# Sheet1.net
KiCad netlist of a schematic drawn in Altium Designer
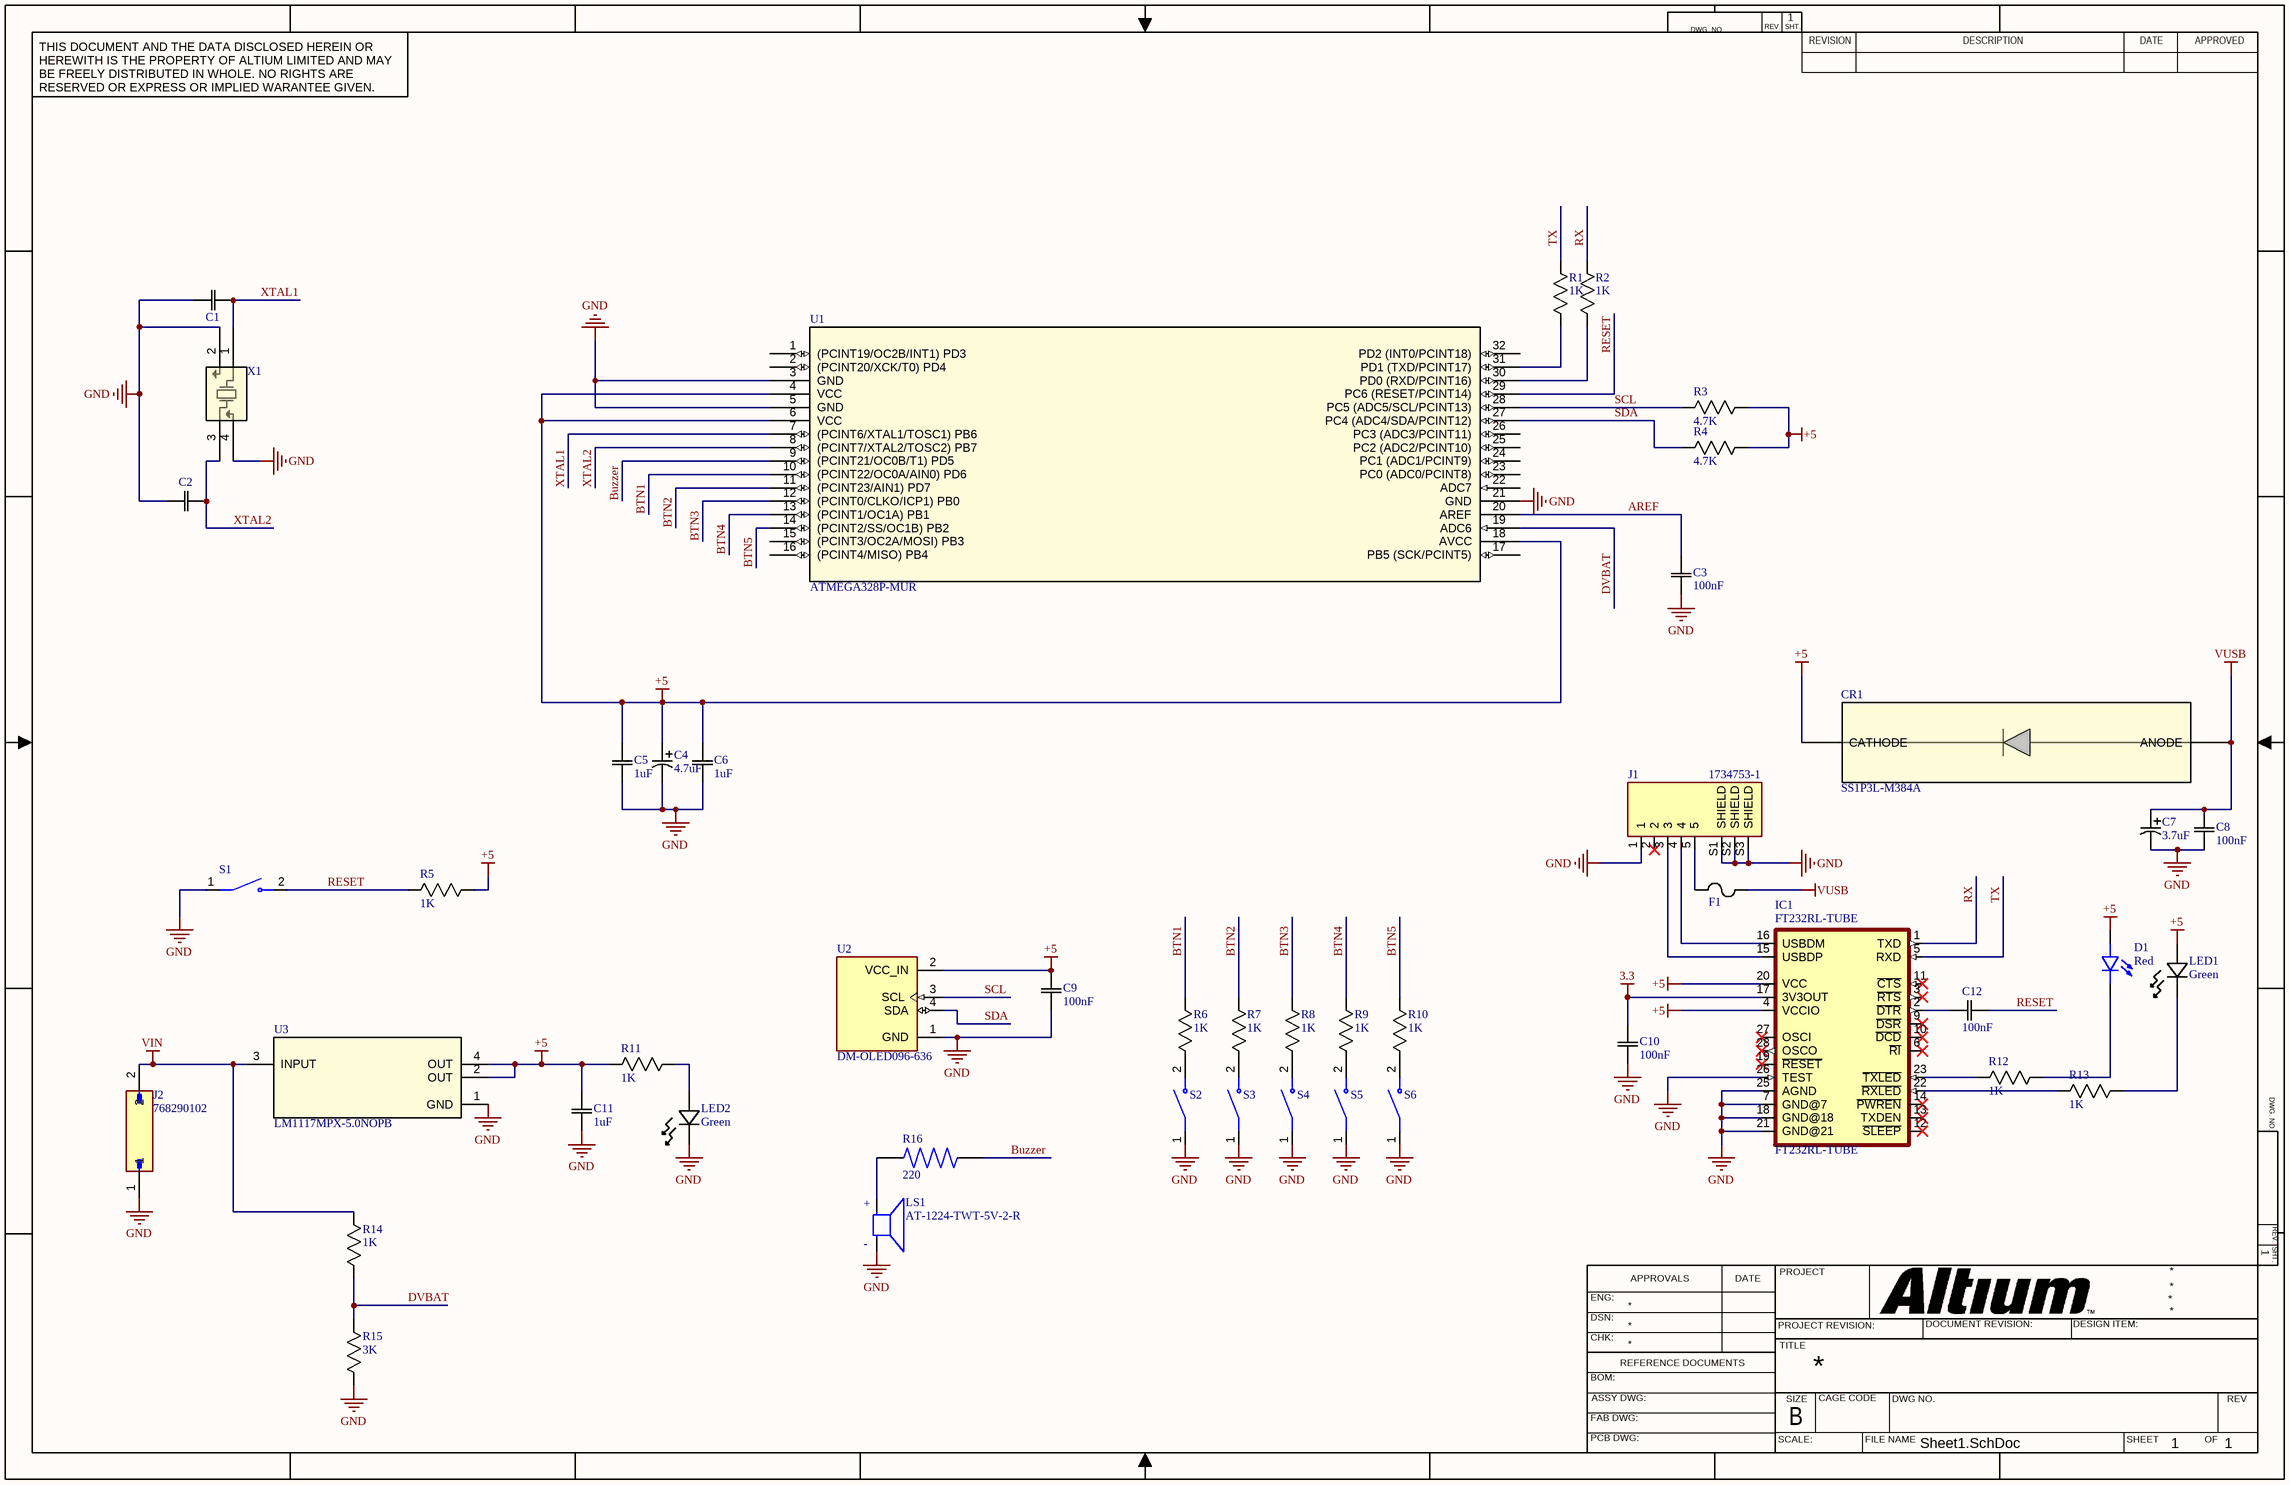
[diagram p0: Sheet1.SchDoc]

(export (version "E")
  (design (tool "Eeschema 10.0.6"))
  (components
    (comp (ref "C1")
      (value "CAP_18pfar_805pkg")
      (footprint "CAP_CC0805_YAG")
      (description "No Description Available")
      (libsource (lib "CAP_18pfar_805pkg") (part "CAP_18pfar_805pkg"))
    )
    (comp (ref "C2")
      (value "CAP_18pfar_805pkg")
      (footprint "CAP_CC0805_YAG")
      (description "No Description Available")
      (libsource (lib "CAP_18pfar_805pkg") (part "CAP_18pfar_805pkg"))
    )
    (comp (ref "C3")
      (value "100nF")
      (footprint "CC0805N_YAG")
      (description "No Description Available")
      (libsource (lib "CAP_100nF_805") (part "CC0805KRX7R9BB104"))
    )
    (comp (ref "C4")
      (value "4.7uF")
      (footprint "CAP_PAN_EEE_B_PAN")
      (description "No Description Available")
      (libsource (lib "CAP_4.7uF_El") (part "EEE-HA1E4R7R"))
    )
    (comp (ref "C5")
      (value "1uF")
      (footprint "CAP_CL21B105KAFNNNE_SAM")
      (description "No Description Available")
      (libsource (lib "CAP_1uF_805") (part "CL21B105KAFNNNE"))
    )
    (comp (ref "C6")
      (value "1uF")
      (footprint "CAP_CL21B105KAFNNNE_SAM")
      (description "No Description Available")
      (libsource (lib "CAP_1uF_805") (part "CL21B105KAFNNNE"))
    )
    (comp (ref "C7")
      (value "3.7uF")
      (footprint "CAP_PAN_EEE_B_PAN")
      (description "No Description Available")
      (libsource (lib "CAP_4.7uF_El") (part "EEE-HA1E4R7R"))
    )
    (comp (ref "C8")
      (value "100nF")
      (footprint "CC0805N_YAG")
      (description "No Description Available")
      (libsource (lib "CAP_100nF_805") (part "CC0805KRX7R9BB104"))
    )
    (comp (ref "C9")
      (value "100nF")
      (footprint "CC0805N_YAG")
      (description "No Description Available")
      (libsource (lib "CAP_100nF_805") (part "CC0805KRX7R9BB104"))
    )
    (comp (ref "C10")
      (value "100nF")
      (footprint "CC0805N_YAG")
      (description "No Description Available")
      (libsource (lib "CAP_100nF_805") (part "CC0805KRX7R9BB104"))
    )
    (comp (ref "C11")
      (value "1uF")
      (footprint "CAP_CL21B105KAFNNNE_SAM")
      (description "No Description Available")
      (libsource (lib "CAP_1uF_805") (part "CL21B105KAFNNNE"))
    )
    (comp (ref "C12")
      (value "100nF")
      (footprint "CC0805N_YAG")
      (description "No Description Available")
      (libsource (lib "CAP_100nF_805") (part "CC0805KRX7R9BB104"))
    )
    (comp (ref "CR1")
      (value "SS1P3L-M384A")
      (footprint "DIODE_SS1P3L-M384A_VIS")
      (description "No Description Available")
      (libsource (lib "SS1P3L-M384A") (part "SS1P3L-M384A"))
    )
    (comp (ref "D1")
      (value "Red")
      (footprint "LED_150060RS75000")
      (fields (field (name "MP") "150060RS75000"))
      (libsource (lib "RedLED") (part "150060RS75000"))
    )
    (comp (ref "F1")
      (value "MF-FSMF050X-2")
      (footprint "FUSE_MF-FSMF050X_BRN")
      (description "No Description Available")
      (libsource (lib "MF-FSMF050X-2") (part "MF-FSMF050X-2"))
    )
    (comp (ref "IC1")
      (value "FT232RL-TUBE")
      (footprint "SSOP28-LD")
      (description "USB Bridge, USB to UART USB 2.0 UART Interface 28-SSOP")
      (fields (field (name "MF") "FTDI,") (field (name "DIGI-KEY_PART_NUMBER") "768-1306-ND"))
      (libsource (lib "FT232RL-TUBE") (part "FT232RL-TUBE"))
    )
    (comp (ref "J1")
      (value "1734753-1")
      (footprint "CONN_1734753-1")
      (description "Conn Mini USB 2.0 Type B RCP 5 POS 0.8mm Solder ST Thru-Hole 5 Terminal 1 Port Box/Tray")
      (fields (field (name "MF") "TE Connectivity"))
      (libsource (lib "1734753-1") (part "1734753-1"))
    )
    (comp (ref "J2")
      (value "768290102")
      (footprint "MOLEX_768290102")
      (libsource (lib "768290102") (part "768290102"))
    )
    (comp (ref "LED1")
      (value "Green")
      (footprint "LED_150060GS75000_WRE")
      (description "No Description Available")
      (libsource (lib "GreenLED") (part "150060GS75000"))
    )
    (comp (ref "LED2")
      (value "Green")
      (footprint "LED_150060GS75000_WRE")
      (description "No Description Available")
      (libsource (lib "GreenLED") (part "150060GS75000"))
    )
    (comp (ref "LS1")
      (value "AT-1224-TWT-5V-2-R")
      (footprint "XDCR_AT-1224-TWT-5V-2-R")
      (description "AUDIO TRANSDUCER 12 VP-P 85 DB 2400 HZ")
      (libsource (lib "AT-1224-TWT-5V-2-R") (part "AT-1224-TWT-5V-2-R"))
    )
    (comp (ref "R1")
      (value "1K")
      (footprint "RC0805N_YAG")
      (description "No Description Available")
      (libsource (lib "RES_1K_805") (part "RC0805FR-071KL"))
    )
    (comp (ref "R2")
      (value "1K")
      (footprint "RC0805N_YAG")
      (description "No Description Available")
      (libsource (lib "RES_1K_805") (part "RC0805FR-071KL"))
    )
    (comp (ref "R3")
      (value "4.7K")
      (footprint "RES_CRCW_0805_VIS")
      (description "No Description Available")
      (libsource (lib "RES_4.7K_805") (part "CRCW08054K70FKEAC"))
    )
    (comp (ref "R4")
      (value "4.7K")
      (footprint "RES_CRCW_0805_VIS")
      (description "No Description Available")
      (libsource (lib "RES_4.7K_805") (part "CRCW08054K70FKEAC"))
    )
    (comp (ref "R5")
      (value "1K")
      (footprint "RC0805N_YAG")
      (description "No Description Available")
      (libsource (lib "RES_1K_805") (part "RC0805FR-071KL"))
    )
    (comp (ref "R6")
      (value "1K")
      (footprint "RC0805N_YAG")
      (description "No Description Available")
      (libsource (lib "RES_1K_805") (part "RC0805FR-071KL"))
    )
    (comp (ref "R7")
      (value "1K")
      (footprint "RC0805N_YAG")
      (description "No Description Available")
      (libsource (lib "RES_1K_805") (part "RC0805FR-071KL"))
    )
    (comp (ref "R8")
      (value "1K")
      (footprint "RC0805N_YAG")
      (description "No Description Available")
      (libsource (lib "RES_1K_805") (part "RC0805FR-071KL"))
    )
    (comp (ref "R9")
      (value "1K")
      (footprint "RC0805N_YAG")
      (description "No Description Available")
      (libsource (lib "RES_1K_805") (part "RC0805FR-071KL"))
    )
    (comp (ref "R10")
      (value "1K")
      (footprint "RC0805N_YAG")
      (description "No Description Available")
      (libsource (lib "RES_1K_805") (part "RC0805FR-071KL"))
    )
    (comp (ref "R11")
      (value "1K")
      (footprint "RC0805N_YAG")
      (description "No Description Available")
      (libsource (lib "RES_1K_805") (part "RC0805FR-071KL"))
    )
    (comp (ref "R12")
      (value "1K")
      (footprint "RC0805N_YAG")
      (description "No Description Available")
      (libsource (lib "RES_1K_805") (part "RC0805FR-071KL"))
    )
    (comp (ref "R13")
      (value "1K")
      (footprint "RC0805N_YAG")
      (description "No Description Available")
      (libsource (lib "RES_1K_805") (part "RC0805FR-071KL"))
    )
    (comp (ref "R14")
      (value "1K")
      (footprint "RC0805N_YAG")
      (description "No Description Available")
      (libsource (lib "RES_1K_805") (part "RC0805FR-071KL"))
    )
    (comp (ref "R15")
      (value "3K")
      (footprint "RES_CRG0805_TEC")
      (description "No Description Available")
      (libsource (lib "RES_3K_805") (part "CRG0805F3K0"))
    )
    (comp (ref "R16")
      (value "220")
      (footprint "RESC2012X65N")
      (description "Fixed Resistor CRGCQ 0805 220R 1%")
      (fields (field (name "MF") "TE Connectivity") (field (name "DIGI-KEY_PART_NUMBER") "A129741CT-ND"))
      (libsource (lib "RES_220_805") (part "CRGCQ0805F220R"))
    )
    (comp (ref "S1")
      (value "PTS636_SM43J_SMTR_LFS")
      (footprint "SW_PTS636_SM43J_SMTR_LFS")
      (description "Tactile Switch SPST-NO Top Actuated Surface Mount")
      (libsource (lib "PTS636_SM43J_SMTR_LFS") (part "PTS636_SM43J_SMTR_LFS"))
    )
    (comp (ref "S2")
      (value "PTS636_SM43J_SMTR_LFS")
      (footprint "SW_PTS636_SM43J_SMTR_LFS")
      (description "Tactile Switch SPST-NO Top Actuated Surface Mount")
      (libsource (lib "PTS636_SM43J_SMTR_LFS") (part "PTS636_SM43J_SMTR_LFS"))
    )
    (comp (ref "S3")
      (value "PTS636_SM43J_SMTR_LFS")
      (footprint "SW_PTS636_SM43J_SMTR_LFS")
      (description "Tactile Switch SPST-NO Top Actuated Surface Mount")
      (libsource (lib "PTS636_SM43J_SMTR_LFS") (part "PTS636_SM43J_SMTR_LFS"))
    )
    (comp (ref "S4")
      (value "PTS636_SM43J_SMTR_LFS")
      (footprint "SW_PTS636_SM43J_SMTR_LFS")
      (description "Tactile Switch SPST-NO Top Actuated Surface Mount")
      (libsource (lib "PTS636_SM43J_SMTR_LFS") (part "PTS636_SM43J_SMTR_LFS"))
    )
    (comp (ref "S5")
      (value "PTS636_SM43J_SMTR_LFS")
      (footprint "SW_PTS636_SM43J_SMTR_LFS")
      (description "Tactile Switch SPST-NO Top Actuated Surface Mount")
      (libsource (lib "PTS636_SM43J_SMTR_LFS") (part "PTS636_SM43J_SMTR_LFS"))
    )
    (comp (ref "S6")
      (value "PTS636_SM43J_SMTR_LFS")
      (footprint "SW_PTS636_SM43J_SMTR_LFS")
      (description "Tactile Switch SPST-NO Top Actuated Surface Mount")
      (libsource (lib "PTS636_SM43J_SMTR_LFS") (part "PTS636_SM43J_SMTR_LFS"))
    )
    (comp (ref "U1")
      (value "ATMEGA328P-MUR")
      (footprint "32M1-A_ATM")
      (description "No Description Available")
      (libsource (lib "ATMEGA328P-MUR") (part "ATMEGA328P-MUR"))
    )
    (comp (ref "U2")
      (value "DM-OLED096-636")
      (footprint "MODULE_DM-OLED096-636")
      (description "0.96â€ 128 X 64 MONOCHROME GRAPHIC OLED DISPLAY MODULE - I2C")
      (fields (field (name "MF") "Display Module"))
      (libsource (lib "DM-OLED096-636") (part "DM-OLED096-636"))
    )
    (comp (ref "U3")
      (value "LM1117MPX-5.0NOPB")
      (footprint "DCY0004A_L")
      (description "No Description Available")
      (libsource (lib "LM1117MPX-5P0NOPB") (part "LM1117MPX-5.0NOPB"))
    )
    (comp (ref "X1")
      (value "ABM8W-16.0000MHZ-8-K1Z-T3")
      (footprint "XTAL4P_ABM8W_ABR")
      (description "No Description Available")
      (libsource (lib "ABM8W-16P0000MHZ-8-K1Z-T3") (part "ABM8W-16.0000MHZ-8-K1Z-T3"))
    )
  )
  (nets
    (net (code "1") (name "+5") (class "Default")
      (node (ref "C11") (pin "2") (pinfunction "2_2") (pintype "passive"))
      (node (ref "C4") (pin "1") (pinfunction "1_1") (pintype "passive"))
      (node (ref "C5") (pin "2") (pinfunction "2_2") (pintype "passive"))
      (node (ref "C6") (pin "2") (pinfunction "2_2") (pintype "passive"))
      (node (ref "C9") (pin "2") (pinfunction "2_2") (pintype "passive"))
      (node (ref "CR1") (pin "1") (pinfunction "CATHODE_1") (pintype "passive"))
      (node (ref "D1") (pin "2") (pinfunction "A_2") (pintype "passive"))
      (node (ref "IC1") (pin "20") (pinfunction "VCC_20") (pintype "power_in"))
      (node (ref "IC1") (pin "4") (pinfunction "VCCIO_4") (pintype "power_in"))
      (node (ref "LED1") (pin "2") (pinfunction "2_2") (pintype "passive"))
      (node (ref "R11") (pin "2") (pinfunction "2_2") (pintype "passive"))
      (node (ref "R3") (pin "2") (pinfunction "2_2") (pintype "passive"))
      (node (ref "R4") (pin "2") (pinfunction "2_2") (pintype "passive"))
      (node (ref "R5") (pin "1") (pinfunction "1_1") (pintype "passive"))
      (node (ref "U1") (pin "18") (pinfunction "AVCC_18") (pintype "power_in"))
      (node (ref "U1") (pin "4") (pinfunction "VCC_4") (pintype "power_in"))
      (node (ref "U1") (pin "6") (pinfunction "VCC_6") (pintype "power_in"))
      (node (ref "U2") (pin "2") (pinfunction "VCC_IN_2") (pintype "power_in"))
      (node (ref "U3") (pin "2") (pinfunction "OUT_2") (pintype "power_in"))
      (node (ref "U3") (pin "4") (pinfunction "OUT_4") (pintype "power_in"))
    )
    (net (code "2") (name "/AREF") (class "Default")
      (node (ref "C3") (pin "2") (pinfunction "2_2") (pintype "passive"))
      (node (ref "U1") (pin "20") (pinfunction "AREF_20") (pintype "passive"))
    )
    (net (code "3") (name "/BTN1") (class "Default")
      (node (ref "R6") (pin "1") (pinfunction "1_1") (pintype "passive"))
      (node (ref "U1") (pin "10") (pinfunction "(PCINT22/OC0A/AIN0)_PD6_10") (pintype "bidirectional"))
    )
    (net (code "4") (name "/BTN2") (class "Default")
      (node (ref "R7") (pin "1") (pinfunction "1_1") (pintype "passive"))
      (node (ref "U1") (pin "11") (pinfunction "(PCINT23/AIN1)_PD7_11") (pintype "bidirectional"))
    )
    (net (code "5") (name "/BTN3") (class "Default")
      (node (ref "R8") (pin "1") (pinfunction "1_1") (pintype "passive"))
      (node (ref "U1") (pin "12") (pinfunction "(PCINT0/CLKO/ICP1)_PB0_12") (pintype "bidirectional"))
    )
    (net (code "6") (name "/BTN4") (class "Default")
      (node (ref "R9") (pin "1") (pinfunction "1_1") (pintype "passive"))
      (node (ref "U1") (pin "13") (pinfunction "(PCINT1/OC1A)_PB1_13") (pintype "bidirectional"))
    )
    (net (code "7") (name "/BTN5") (class "Default")
      (node (ref "R10") (pin "1") (pinfunction "1_1") (pintype "passive"))
      (node (ref "U1") (pin "14") (pinfunction "(PCINT2/SS/OC1B)_PB2_14") (pintype "bidirectional"))
    )
    (net (code "8") (name "/Buzzer") (class "Default")
      (node (ref "R16") (pin "2") (pinfunction "2_2") (pintype "passive"))
      (node (ref "U1") (pin "9") (pinfunction "(PCINT21/OC0B/T1)_PD5_9") (pintype "bidirectional"))
    )
    (net (code "9") (name "/DVBAT") (class "Default")
      (node (ref "R14") (pin "2") (pinfunction "2_2") (pintype "passive"))
      (node (ref "R15") (pin "2") (pinfunction "2_2") (pintype "passive"))
      (node (ref "U1") (pin "19") (pinfunction "ADC6_19") (pintype "input"))
    )
    (net (code "10") (name "/RESET") (class "Default")
      (node (ref "C12") (pin "1") (pinfunction "1_1") (pintype "passive"))
      (node (ref "R5") (pin "2") (pinfunction "2_2") (pintype "passive"))
      (node (ref "S1") (pin "2") (pinfunction "NO_2") (pintype "passive"))
      (node (ref "U1") (pin "29") (pinfunction "PC6_(RESET/PCINT14)_29") (pintype "bidirectional"))
    )
    (net (code "11") (name "/RX") (class "Default")
      (node (ref "IC1") (pin "1") (pinfunction "TXD_1") (pintype "output"))
      (node (ref "R2") (pin "1") (pinfunction "1_1") (pintype "passive"))
    )
    (net (code "12") (name "/SCL") (class "Default")
      (node (ref "R3") (pin "1") (pinfunction "1_1") (pintype "passive"))
      (node (ref "U1") (pin "28") (pinfunction "PC5_(ADC5/SCL/PCINT13)_28") (pintype "bidirectional"))
      (node (ref "U2") (pin "3") (pinfunction "SCL_3") (pintype "input"))
    )
    (net (code "13") (name "/SDA") (class "Default")
      (node (ref "R4") (pin "1") (pinfunction "1_1") (pintype "passive"))
      (node (ref "U1") (pin "27") (pinfunction "PC4_(ADC4/SDA/PCINT12)_27") (pintype "bidirectional"))
      (node (ref "U2") (pin "4") (pinfunction "SDA_4") (pintype "bidirectional"))
    )
    (net (code "14") (name "/TX") (class "Default")
      (node (ref "IC1") (pin "5") (pinfunction "RXD_5") (pintype "input"))
      (node (ref "R1") (pin "1") (pinfunction "1_1") (pintype "passive"))
    )
    (net (code "15") (name "/XTAL1") (class "Default")
      (node (ref "C1") (pin "1") (pinfunction "1_1") (pintype "passive"))
      (node (ref "U1") (pin "7") (pinfunction "(PCINT6/XTAL1/TOSC1)_PB6_7") (pintype "bidirectional"))
      (node (ref "X1") (pin "1") (pinfunction "1_1") (pintype "passive"))
    )
    (net (code "16") (name "/XTAL2") (class "Default")
      (node (ref "C2") (pin "2") (pinfunction "2_2") (pintype "passive"))
      (node (ref "U1") (pin "8") (pinfunction "(PCINT7/XTAL2/TOSC2)_PB7_8") (pintype "bidirectional"))
      (node (ref "X1") (pin "3") (pinfunction "3_3") (pintype "passive"))
    )
    (net (code "17") (name "3.3") (class "Default")
      (node (ref "C10") (pin "2") (pinfunction "2_2") (pintype "passive"))
      (node (ref "IC1") (pin "17") (pinfunction "3V3OUT_17") (pintype "power_in"))
    )
    (net (code "18") (name "GND") (class "Default")
      (node (ref "C1") (pin "2") (pinfunction "2_2") (pintype "passive"))
      (node (ref "C10") (pin "1") (pinfunction "1_1") (pintype "passive"))
      (node (ref "C11") (pin "1") (pinfunction "1_1") (pintype "passive"))
      (node (ref "C2") (pin "1") (pinfunction "1_1") (pintype "passive"))
      (node (ref "C3") (pin "1") (pinfunction "1_1") (pintype "passive"))
      (node (ref "C4") (pin "2") (pinfunction "2_2") (pintype "passive"))
      (node (ref "C5") (pin "1") (pinfunction "1_1") (pintype "passive"))
      (node (ref "C6") (pin "1") (pinfunction "1_1") (pintype "passive"))
      (node (ref "C7") (pin "2") (pinfunction "2_2") (pintype "passive"))
      (node (ref "C8") (pin "1") (pinfunction "1_1") (pintype "passive"))
      (node (ref "C9") (pin "1") (pinfunction "1_1") (pintype "passive"))
      (node (ref "IC1") (pin "18") (pinfunction "GND@18_18") (pintype "power_in"))
      (node (ref "IC1") (pin "21") (pinfunction "GND@21_21") (pintype "power_in"))
      (node (ref "IC1") (pin "25") (pinfunction "AGND_25") (pintype "power_in"))
      (node (ref "IC1") (pin "26") (pinfunction "TEST_26") (pintype "input"))
      (node (ref "IC1") (pin "7") (pinfunction "GND@7_7") (pintype "power_in"))
      (node (ref "J1") (pin "1") (pinfunction "1_1") (pintype "passive"))
      (node (ref "J1") (pin "S1") (pinfunction "SHIELD_S1") (pintype "passive"))
      (node (ref "J1") (pin "S2") (pinfunction "SHIELD_S2") (pintype "passive"))
      (node (ref "J1") (pin "S3") (pinfunction "SHIELD_S3") (pintype "passive"))
      (node (ref "J2") (pin "1") (pinfunction "1_1") (pintype "passive"))
      (node (ref "LED2") (pin "1") (pinfunction "1_1") (pintype "passive"))
      (node (ref "LS1") (pin "N") (pinfunction "N_N") (pintype "passive"))
      (node (ref "R15") (pin "1") (pinfunction "1_1") (pintype "passive"))
      (node (ref "S1") (pin "1") (pinfunction "COM_1") (pintype "passive"))
      (node (ref "S2") (pin "1") (pinfunction "COM_1") (pintype "passive"))
      (node (ref "S3") (pin "1") (pinfunction "COM_1") (pintype "passive"))
      (node (ref "S4") (pin "1") (pinfunction "COM_1") (pintype "passive"))
      (node (ref "S5") (pin "1") (pinfunction "COM_1") (pintype "passive"))
      (node (ref "S6") (pin "1") (pinfunction "COM_1") (pintype "passive"))
      (node (ref "U1") (pin "21") (pinfunction "GND_21") (pintype "power_in"))
      (node (ref "U1") (pin "3") (pinfunction "GND_3") (pintype "power_in"))
      (node (ref "U1") (pin "5") (pinfunction "GND_5") (pintype "power_in"))
      (node (ref "U2") (pin "1") (pinfunction "GND_1") (pintype "power_in"))
      (node (ref "U3") (pin "1") (pinfunction "GND_1") (pintype "power_in"))
      (node (ref "X1") (pin "2") (pinfunction "2_2") (pintype "passive"))
      (node (ref "X1") (pin "4") (pinfunction "4_4") (pintype "passive"))
    )
    (net (code "19") (name "Net-(D1-C)") (class "Default")
      (node (ref "D1") (pin "1") (pinfunction "C_1") (pintype "passive"))
      (node (ref "R12") (pin "1") (pinfunction "1_1") (pintype "passive"))
    )
    (net (code "20") (name "Net-(F1-Pad1)") (class "Default")
      (node (ref "F1") (pin "1") (pinfunction "1_1") (pintype "passive"))
      (node (ref "J1") (pin "5") (pinfunction "5_5") (pintype "passive"))
    )
    (net (code "21") (name "Net-(IC1-USBDM)") (class "Default")
      (node (ref "IC1") (pin "16") (pinfunction "USBDM_16") (pintype "bidirectional"))
      (node (ref "J1") (pin "4") (pinfunction "4_4") (pintype "passive"))
    )
    (net (code "22") (name "Net-(IC1-USBDP)") (class "Default")
      (node (ref "IC1") (pin "15") (pinfunction "USBDP_15") (pintype "bidirectional"))
      (node (ref "J1") (pin "3") (pinfunction "3_3") (pintype "passive"))
    )
    (net (code "23") (name "Net-(IC1-~{DTR})") (class "Default")
      (node (ref "C12") (pin "2") (pinfunction "2_2") (pintype "passive"))
      (node (ref "IC1") (pin "2") (pinfunction "~{DTR}_2") (pintype "output"))
    )
    (net (code "24") (name "Net-(IC1-~{RXLED})") (class "Default")
      (node (ref "IC1") (pin "22") (pinfunction "~{RXLED}_22") (pintype "input"))
      (node (ref "R13") (pin "2") (pinfunction "2_2") (pintype "passive"))
    )
    (net (code "25") (name "Net-(IC1-~{TXLED})") (class "Default")
      (node (ref "IC1") (pin "23") (pinfunction "~{TXLED}_23") (pintype "input"))
      (node (ref "R12") (pin "2") (pinfunction "2_2") (pintype "passive"))
    )
    (net (code "26") (name "Net-(LED1-Pad1)") (class "Default")
      (node (ref "LED1") (pin "1") (pinfunction "1_1") (pintype "passive"))
      (node (ref "R13") (pin "1") (pinfunction "1_1") (pintype "passive"))
    )
    (net (code "27") (name "Net-(LED2-Pad2)") (class "Default")
      (node (ref "LED2") (pin "2") (pinfunction "2_2") (pintype "passive"))
      (node (ref "R11") (pin "1") (pinfunction "1_1") (pintype "passive"))
    )
    (net (code "28") (name "Net-(LS1-PadP)") (class "Default")
      (node (ref "LS1") (pin "P") (pinfunction "P_P") (pintype "passive"))
      (node (ref "R16") (pin "1") (pinfunction "1_1") (pintype "passive"))
    )
    (net (code "29") (name "Net-(S2-NO)") (class "Default")
      (node (ref "R6") (pin "2") (pinfunction "2_2") (pintype "passive"))
      (node (ref "S2") (pin "2") (pinfunction "NO_2") (pintype "passive"))
    )
    (net (code "30") (name "Net-(S3-NO)") (class "Default")
      (node (ref "R7") (pin "2") (pinfunction "2_2") (pintype "passive"))
      (node (ref "S3") (pin "2") (pinfunction "NO_2") (pintype "passive"))
    )
    (net (code "31") (name "Net-(S4-NO)") (class "Default")
      (node (ref "R8") (pin "2") (pinfunction "2_2") (pintype "passive"))
      (node (ref "S4") (pin "2") (pinfunction "NO_2") (pintype "passive"))
    )
    (net (code "32") (name "Net-(S5-NO)") (class "Default")
      (node (ref "R9") (pin "2") (pinfunction "2_2") (pintype "passive"))
      (node (ref "S5") (pin "2") (pinfunction "NO_2") (pintype "passive"))
    )
    (net (code "33") (name "Net-(S6-NO)") (class "Default")
      (node (ref "R10") (pin "2") (pinfunction "2_2") (pintype "passive"))
      (node (ref "S6") (pin "2") (pinfunction "NO_2") (pintype "passive"))
    )
    (net (code "34") (name "Net-(U1-PD0_(RXD{slash}PCINT16))") (class "Default")
      (node (ref "R2") (pin "2") (pinfunction "2_2") (pintype "passive"))
      (node (ref "U1") (pin "30") (pinfunction "PD0_(RXD/PCINT16)_30") (pintype "bidirectional"))
    )
    (net (code "35") (name "Net-(U1-PD1_(TXD{slash}PCINT17))") (class "Default")
      (node (ref "R1") (pin "2") (pinfunction "2_2") (pintype "passive"))
      (node (ref "U1") (pin "31") (pinfunction "PD1_(TXD/PCINT17)_31") (pintype "bidirectional"))
    )
    (net (code "36") (name "VIN") (class "Default")
      (node (ref "J2") (pin "2") (pinfunction "2_2") (pintype "passive"))
      (node (ref "R14") (pin "1") (pinfunction "1_1") (pintype "passive"))
      (node (ref "U3") (pin "3") (pinfunction "INPUT_3") (pintype "power_in"))
    )
    (net (code "37") (name "VUSB") (class "Default")
      (node (ref "C7") (pin "1") (pinfunction "1_1") (pintype "passive"))
      (node (ref "C8") (pin "2") (pinfunction "2_2") (pintype "passive"))
      (node (ref "CR1") (pin "2") (pinfunction "ANODE_2") (pintype "passive"))
      (node (ref "F1") (pin "2") (pinfunction "2_2") (pintype "passive"))
    )
    (net (code "38") (name "unconnected-(IC1-OSCI-Pad27)") (class "Default")
      (node (ref "IC1") (pin "27") (pinfunction "OSCI_27") (pintype "passive+no_connect"))
    )
    (net (code "39") (name "unconnected-(IC1-OSCO-Pad28)") (class "Default")
      (node (ref "IC1") (pin "28") (pinfunction "OSCO_28") (pintype "output+no_connect"))
    )
    (net (code "40") (name "unconnected-(IC1-TXDEN-Pad13)") (class "Default")
      (node (ref "IC1") (pin "13") (pinfunction "TXDEN_13") (pintype "passive+no_connect"))
    )
    (net (code "41") (name "unconnected-(IC1-~{CTS}-Pad11)") (class "Default")
      (node (ref "IC1") (pin "11") (pinfunction "~{CTS}_11") (pintype "input+no_connect"))
    )
    (net (code "42") (name "unconnected-(IC1-~{DCD}-Pad10)") (class "Default")
      (node (ref "IC1") (pin "10") (pinfunction "~{DCD}_10") (pintype "passive+no_connect"))
    )
    (net (code "43") (name "unconnected-(IC1-~{DSR}-Pad9)") (class "Default")
      (node (ref "IC1") (pin "9") (pinfunction "~{DSR}_9") (pintype "passive+no_connect"))
    )
    (net (code "44") (name "unconnected-(IC1-~{PWREN}-Pad14)") (class "Default")
      (node (ref "IC1") (pin "14") (pinfunction "~{PWREN}_14") (pintype "passive+no_connect"))
    )
    (net (code "45") (name "unconnected-(IC1-~{RESET}-Pad19)") (class "Default")
      (node (ref "IC1") (pin "19") (pinfunction "~{RESET}_19") (pintype "passive+no_connect"))
    )
    (net (code "46") (name "unconnected-(IC1-~{RI}-Pad6)") (class "Default")
      (node (ref "IC1") (pin "6") (pinfunction "~{RI}_6") (pintype "passive+no_connect"))
    )
    (net (code "47") (name "unconnected-(IC1-~{RTS}-Pad3)") (class "Default")
      (node (ref "IC1") (pin "3") (pinfunction "~{RTS}_3") (pintype "output+no_connect"))
    )
    (net (code "48") (name "unconnected-(IC1-~{SLEEP}-Pad12)") (class "Default")
      (node (ref "IC1") (pin "12") (pinfunction "~{SLEEP}_12") (pintype "passive+no_connect"))
    )
    (net (code "49") (name "unconnected-(J1-Pad2)") (class "Default")
      (node (ref "J1") (pin "2") (pinfunction "2_2") (pintype "passive+no_connect"))
    )
    (net (code "50") (name "unconnected-(U1-(PCINT3{slash}OC2A{slash}MOSI)_PB3-Pad15)") (class "Default")
      (node (ref "U1") (pin "15") (pinfunction "(PCINT3/OC2A/MOSI)_PB3_15") (pintype "bidirectional"))
    )
    (net (code "51") (name "unconnected-(U1-(PCINT4{slash}MISO)_PB4-Pad16)") (class "Default")
      (node (ref "U1") (pin "16") (pinfunction "(PCINT4/MISO)_PB4_16") (pintype "bidirectional"))
    )
    (net (code "52") (name "unconnected-(U1-(PCINT19{slash}OC2B{slash}INT1)_PD3-Pad1)") (class "Default")
      (node (ref "U1") (pin "1") (pinfunction "(PCINT19/OC2B/INT1)_PD3_1") (pintype "bidirectional"))
    )
    (net (code "53") (name "unconnected-(U1-(PCINT20{slash}XCK{slash}T0)_PD4-Pad2)") (class "Default")
      (node (ref "U1") (pin "2") (pinfunction "(PCINT20/XCK/T0)_PD4_2") (pintype "bidirectional"))
    )
    (net (code "54") (name "unconnected-(U1-ADC7-Pad22)") (class "Default")
      (node (ref "U1") (pin "22") (pinfunction "ADC7_22") (pintype "input"))
    )
    (net (code "55") (name "unconnected-(U1-PB5_(SCK{slash}PCINT5)-Pad17)") (class "Default")
      (node (ref "U1") (pin "17") (pinfunction "PB5_(SCK/PCINT5)_17") (pintype "bidirectional"))
    )
    (net (code "56") (name "unconnected-(U1-PC0_(ADC0{slash}PCINT8)-Pad23)") (class "Default")
      (node (ref "U1") (pin "23") (pinfunction "PC0_(ADC0/PCINT8)_23") (pintype "bidirectional"))
    )
    (net (code "57") (name "unconnected-(U1-PC1_(ADC1{slash}PCINT9)-Pad24)") (class "Default")
      (node (ref "U1") (pin "24") (pinfunction "PC1_(ADC1/PCINT9)_24") (pintype "bidirectional"))
    )
    (net (code "58") (name "unconnected-(U1-PC2_(ADC2{slash}PCINT10)-Pad25)") (class "Default")
      (node (ref "U1") (pin "25") (pinfunction "PC2_(ADC2/PCINT10)_25") (pintype "bidirectional"))
    )
    (net (code "59") (name "unconnected-(U1-PC3_(ADC3{slash}PCINT11)-Pad26)") (class "Default")
      (node (ref "U1") (pin "26") (pinfunction "PC3_(ADC3/PCINT11)_26") (pintype "bidirectional"))
    )
    (net (code "60") (name "unconnected-(U1-PD2_(INT0{slash}PCINT18)-Pad32)") (class "Default")
      (node (ref "U1") (pin "32") (pinfunction "PD2_(INT0/PCINT18)_32") (pintype "bidirectional"))
    )
  )
)
